# Sch5PowerControlCenter.net
KiCad netlist of a schematic drawn in Altium Designer
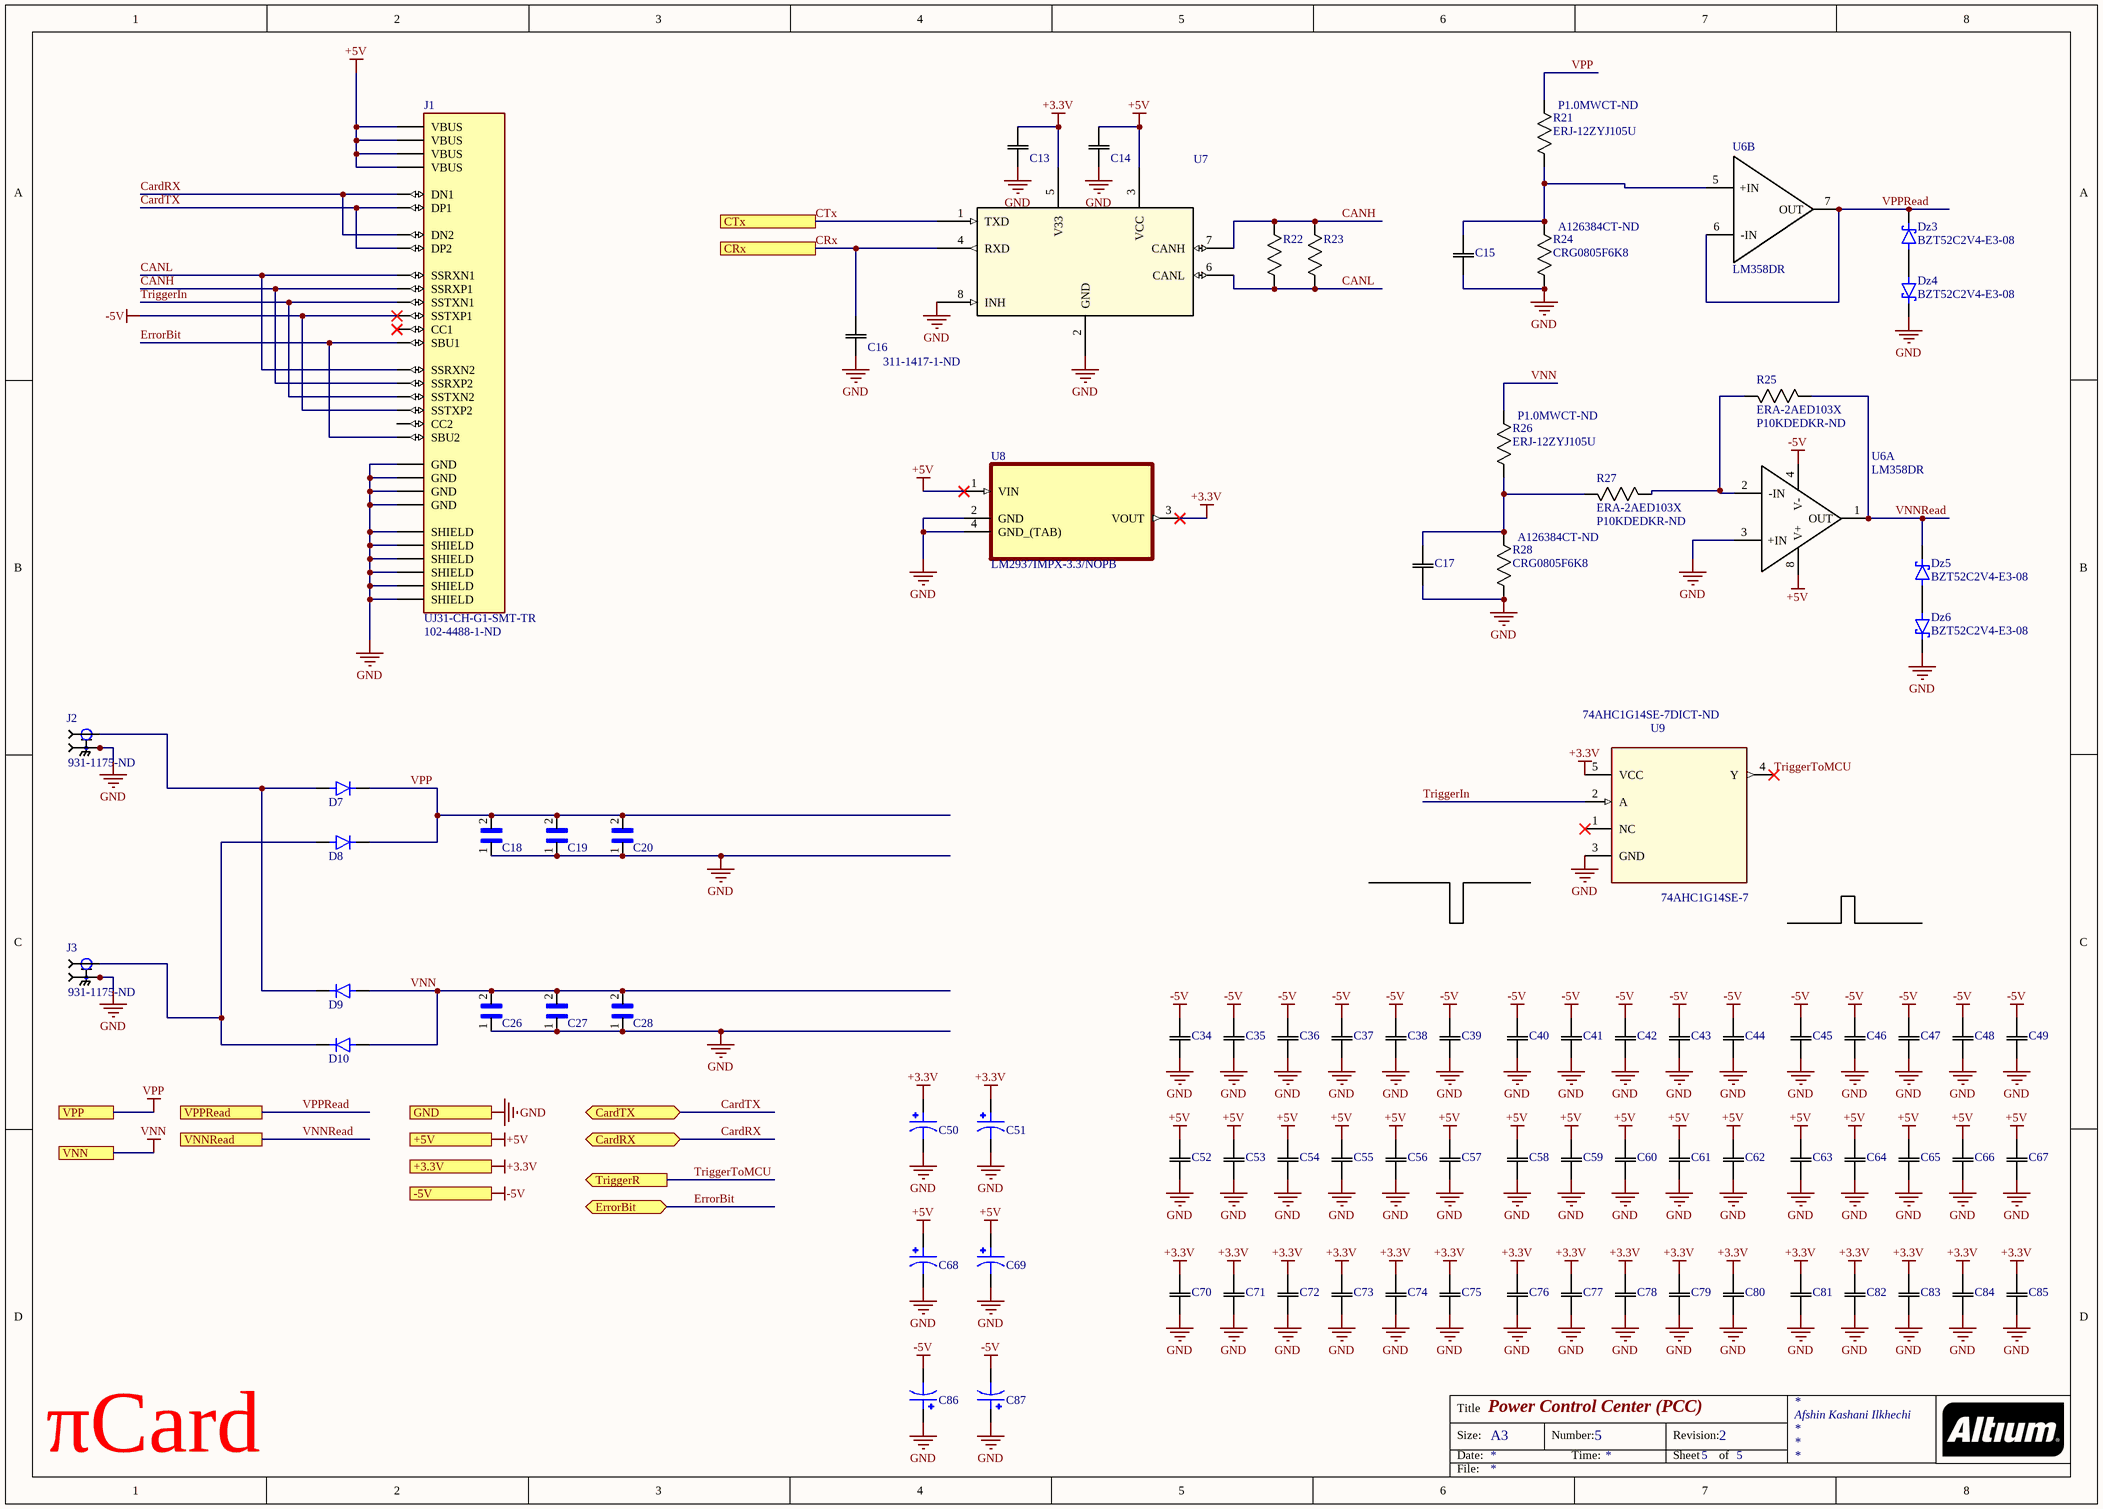
[diagram p0: Sch5PowerControlCenter.SchDoc]

(export (version "E")
  (design (tool "Eeschema 10.0.6"))
  (components
    (comp (ref "C13")
      (value "GRM155R71C103MA01D")
      (footprint "C0402")
      (libsource (lib "Afshin Library") (part "Cap_0402"))
    )
    (comp (ref "C14")
      (value "GRM155R71C103MA01D")
      (footprint "C0402")
      (libsource (lib "Afshin Library") (part "Cap_0402"))
    )
    (comp (ref "C15")
      (value "C0805C104Z5VACTU")
      (footprint "C0805")
      (libsource (lib "Afshin Library") (part "Cap_0805"))
    )
    (comp (ref "C16")
      (value "CC0402JRNPO9BN200")
      (footprint "C0402")
      (fields (field (name "SUPPLIER PART NUMBER 1") "311-1417-1-ND"))
      (libsource (lib "Afshin Library") (part "Cap_0402"))
    )
    (comp (ref "C17")
      (value "C0805C104Z5VACTU")
      (footprint "C0805")
      (libsource (lib "Afshin Library") (part "Cap_0805"))
    )
    (comp (ref "C18")
      (value "2220Y5000105KXTWS2")
      (footprint "CAPC5750X450N")
      (description "1ÂµF Â±10% 500V Ceramic Capacitor X7R 2220 (5750 Metric)")
      (fields (field (name "MF") "Syfer"))
      (libsource (lib "Afshin Library") (part "2220Y5000105KXTWS2"))
    )
    (comp (ref "C19")
      (value "2220Y5000105KXTWS2")
      (footprint "CAPC5750X450N")
      (description "1ÂµF Â±10% 500V Ceramic Capacitor X7R 2220 (5750 Metric)")
      (fields (field (name "MF") "Syfer"))
      (libsource (lib "Afshin Library") (part "2220Y5000105KXTWS2"))
    )
    (comp (ref "C20")
      (value "2220Y5000105KXTWS2")
      (footprint "CAPC5750X450N")
      (description "1ÂµF Â±10% 500V Ceramic Capacitor X7R 2220 (5750 Metric)")
      (fields (field (name "MF") "Syfer"))
      (libsource (lib "Afshin Library") (part "2220Y5000105KXTWS2"))
    )
    (comp (ref "C26")
      (value "2220Y5000105KXTWS2")
      (footprint "CAPC5750X450N")
      (description "1ÂµF Â±10% 500V Ceramic Capacitor X7R 2220 (5750 Metric)")
      (fields (field (name "MF") "Syfer"))
      (libsource (lib "Afshin Library") (part "2220Y5000105KXTWS2"))
    )
    (comp (ref "C27")
      (value "2220Y5000105KXTWS2")
      (footprint "CAPC5750X450N")
      (description "1ÂµF Â±10% 500V Ceramic Capacitor X7R 2220 (5750 Metric)")
      (fields (field (name "MF") "Syfer"))
      (libsource (lib "Afshin Library") (part "2220Y5000105KXTWS2"))
    )
    (comp (ref "C28")
      (value "2220Y5000105KXTWS2")
      (footprint "CAPC5750X450N")
      (description "1ÂµF Â±10% 500V Ceramic Capacitor X7R 2220 (5750 Metric)")
      (fields (field (name "MF") "Syfer"))
      (libsource (lib "Afshin Library") (part "2220Y5000105KXTWS2"))
    )
    (comp (ref "C34")
      (value "GRM155R71C103MA01D")
      (footprint "C0402")
      (libsource (lib "Afshin Library") (part "Cap_0402"))
    )
    (comp (ref "C35")
      (value "GRM155R71C103MA01D")
      (footprint "C0402")
      (libsource (lib "Afshin Library") (part "Cap_0402"))
    )
    (comp (ref "C36")
      (value "GRM155R71C103MA01D")
      (footprint "C0402")
      (libsource (lib "Afshin Library") (part "Cap_0402"))
    )
    (comp (ref "C37")
      (value "GRM155R71C103MA01D")
      (footprint "C0402")
      (libsource (lib "Afshin Library") (part "Cap_0402"))
    )
    (comp (ref "C38")
      (value "GRM155R71C103MA01D")
      (footprint "C0402")
      (libsource (lib "Afshin Library") (part "Cap_0402"))
    )
    (comp (ref "C39")
      (value "GRM155R71C103MA01D")
      (footprint "C0402")
      (libsource (lib "Afshin Library") (part "Cap_0402"))
    )
    (comp (ref "C40")
      (value "C0805C104Z5VACTU")
      (footprint "C0805")
      (libsource (lib "Afshin Library") (part "Cap_0805"))
    )
    (comp (ref "C41")
      (value "C0805C104Z5VACTU")
      (footprint "C0805")
      (libsource (lib "Afshin Library") (part "Cap_0805"))
    )
    (comp (ref "C42")
      (value "C0805C104Z5VACTU")
      (footprint "C0805")
      (libsource (lib "Afshin Library") (part "Cap_0805"))
    )
    (comp (ref "C43")
      (value "C0805C104Z5VACTU")
      (footprint "C0805")
      (libsource (lib "Afshin Library") (part "Cap_0805"))
    )
    (comp (ref "C44")
      (value "C0805C104Z5VACTU")
      (footprint "C0805")
      (libsource (lib "Afshin Library") (part "Cap_0805"))
    )
    (comp (ref "C45")
      (value "GRM155R71H102KA01J")
      (footprint "C0402")
      (libsource (lib "Afshin Library") (part "Cap_0402"))
    )
    (comp (ref "C46")
      (value "GRM155R71H102KA01J")
      (footprint "C0402")
      (libsource (lib "Afshin Library") (part "Cap_0402"))
    )
    (comp (ref "C47")
      (value "GRM155R71H102KA01J")
      (footprint "C0402")
      (libsource (lib "Afshin Library") (part "Cap_0402"))
    )
    (comp (ref "C48")
      (value "GRM155R71H102KA01J")
      (footprint "C0402")
      (libsource (lib "Afshin Library") (part "Cap_0402"))
    )
    (comp (ref "C49")
      (value "GRM155R71H102KA01J")
      (footprint "C0402")
      (libsource (lib "Afshin Library") (part "Cap_0402"))
    )
    (comp (ref "C50")
      (value "T55A107M6R3C0200")
      (footprint "C1206")
      (description "Tantalium")
      (libsource (lib "Afshin Library") (part "Cap_1206"))
    )
    (comp (ref "C51")
      (value "T55A107M6R3C0200")
      (footprint "C1206")
      (description "Tantalium")
      (libsource (lib "Afshin Library") (part "Cap_1206"))
    )
    (comp (ref "C52")
      (value "GRM155R71C103MA01D")
      (footprint "C0402")
      (libsource (lib "Afshin Library") (part "Cap_0402"))
    )
    (comp (ref "C53")
      (value "GRM155R71C103MA01D")
      (footprint "C0402")
      (libsource (lib "Afshin Library") (part "Cap_0402"))
    )
    (comp (ref "C54")
      (value "GRM155R71C103MA01D")
      (footprint "C0402")
      (libsource (lib "Afshin Library") (part "Cap_0402"))
    )
    (comp (ref "C55")
      (value "GRM155R71C103MA01D")
      (footprint "C0402")
      (libsource (lib "Afshin Library") (part "Cap_0402"))
    )
    (comp (ref "C56")
      (value "GRM155R71C103MA01D")
      (footprint "C0402")
      (libsource (lib "Afshin Library") (part "Cap_0402"))
    )
    (comp (ref "C57")
      (value "GRM155R71C103MA01D")
      (footprint "C0402")
      (libsource (lib "Afshin Library") (part "Cap_0402"))
    )
    (comp (ref "C58")
      (value "C0805C104Z5VACTU")
      (footprint "C0805")
      (libsource (lib "Afshin Library") (part "Cap_0805"))
    )
    (comp (ref "C59")
      (value "C0805C104Z5VACTU")
      (footprint "C0805")
      (libsource (lib "Afshin Library") (part "Cap_0805"))
    )
    (comp (ref "C60")
      (value "C0805C104Z5VACTU")
      (footprint "C0805")
      (libsource (lib "Afshin Library") (part "Cap_0805"))
    )
    (comp (ref "C61")
      (value "C0805C104Z5VACTU")
      (footprint "C0805")
      (libsource (lib "Afshin Library") (part "Cap_0805"))
    )
    (comp (ref "C62")
      (value "C0805C104Z5VACTU")
      (footprint "C0805")
      (libsource (lib "Afshin Library") (part "Cap_0805"))
    )
    (comp (ref "C63")
      (value "GRM155R71H102KA01J")
      (footprint "C0402")
      (libsource (lib "Afshin Library") (part "Cap_0402"))
    )
    (comp (ref "C64")
      (value "GRM155R71H102KA01J")
      (footprint "C0402")
      (libsource (lib "Afshin Library") (part "Cap_0402"))
    )
    (comp (ref "C65")
      (value "GRM155R71H102KA01J")
      (footprint "C0402")
      (libsource (lib "Afshin Library") (part "Cap_0402"))
    )
    (comp (ref "C66")
      (value "GRM155R71H102KA01J")
      (footprint "C0402")
      (libsource (lib "Afshin Library") (part "Cap_0402"))
    )
    (comp (ref "C67")
      (value "GRM155R71H102KA01J")
      (footprint "C0402")
      (libsource (lib "Afshin Library") (part "Cap_0402"))
    )
    (comp (ref "C68")
      (value "T55A107M6R3C0200")
      (footprint "C1206")
      (description "Tantalium")
      (libsource (lib "Afshin Library") (part "Cap_1206"))
    )
    (comp (ref "C69")
      (value "T55A107M6R3C0200")
      (footprint "C1206")
      (description "Tantalium")
      (libsource (lib "Afshin Library") (part "Cap_1206"))
    )
    (comp (ref "C70")
      (value "GRM155R71C103MA01D")
      (footprint "C0402")
      (libsource (lib "Afshin Library") (part "Cap_0402"))
    )
    (comp (ref "C71")
      (value "GRM155R71C103MA01D")
      (footprint "C0402")
      (libsource (lib "Afshin Library") (part "Cap_0402"))
    )
    (comp (ref "C72")
      (value "GRM155R71C103MA01D")
      (footprint "C0402")
      (libsource (lib "Afshin Library") (part "Cap_0402"))
    )
    (comp (ref "C73")
      (value "GRM155R71C103MA01D")
      (footprint "C0402")
      (libsource (lib "Afshin Library") (part "Cap_0402"))
    )
    (comp (ref "C74")
      (value "GRM155R71C103MA01D")
      (footprint "C0402")
      (libsource (lib "Afshin Library") (part "Cap_0402"))
    )
    (comp (ref "C75")
      (value "GRM155R71C103MA01D")
      (footprint "C0402")
      (libsource (lib "Afshin Library") (part "Cap_0402"))
    )
    (comp (ref "C76")
      (value "C0805C104Z5VACTU")
      (footprint "C0805")
      (libsource (lib "Afshin Library") (part "Cap_0805"))
    )
    (comp (ref "C77")
      (value "C0805C104Z5VACTU")
      (footprint "C0805")
      (libsource (lib "Afshin Library") (part "Cap_0805"))
    )
    (comp (ref "C78")
      (value "C0805C104Z5VACTU")
      (footprint "C0805")
      (libsource (lib "Afshin Library") (part "Cap_0805"))
    )
    (comp (ref "C79")
      (value "C0805C104Z5VACTU")
      (footprint "C0805")
      (libsource (lib "Afshin Library") (part "Cap_0805"))
    )
    (comp (ref "C80")
      (value "C0805C104Z5VACTU")
      (footprint "C0805")
      (libsource (lib "Afshin Library") (part "Cap_0805"))
    )
    (comp (ref "C81")
      (value "GRM155R71H102KA01J")
      (footprint "C0402")
      (libsource (lib "Afshin Library") (part "Cap_0402"))
    )
    (comp (ref "C82")
      (value "GRM155R71H102KA01J")
      (footprint "C0402")
      (libsource (lib "Afshin Library") (part "Cap_0402"))
    )
    (comp (ref "C83")
      (value "GRM155R71H102KA01J")
      (footprint "C0402")
      (libsource (lib "Afshin Library") (part "Cap_0402"))
    )
    (comp (ref "C84")
      (value "GRM155R71H102KA01J")
      (footprint "C0402")
      (libsource (lib "Afshin Library") (part "Cap_0402"))
    )
    (comp (ref "C85")
      (value "GRM155R71H102KA01J")
      (footprint "C0402")
      (libsource (lib "Afshin Library") (part "Cap_0402"))
    )
    (comp (ref "C86")
      (value "T55A107M6R3C0200")
      (footprint "C1206")
      (description "Tantalium")
      (libsource (lib "") (part "Cap_1206_1"))
    )
    (comp (ref "C87")
      (value "T55A107M6R3C0200")
      (footprint "C1206")
      (description "Tantalium")
      (libsource (lib "") (part "Cap_1206_1"))
    )
    (comp (ref "D7")
      (value "CD1408-R11000")
      (footprint "CD1408")
      (description "Diode Standard 1000V 1A Surface Mount 1408")
      (libsource (lib "Afshin Library") (part "CD1408-R11000"))
    )
    (comp (ref "D8")
      (value "CD1408-R11000")
      (footprint "CD1408")
      (description "Diode Standard 1000V 1A Surface Mount 1408")
      (libsource (lib "Afshin Library") (part "CD1408-R11000"))
    )
    (comp (ref "D9")
      (value "CD1408-R11000")
      (footprint "CD1408")
      (description "Diode Standard 1000V 1A Surface Mount 1408")
      (libsource (lib "Afshin Library") (part "CD1408-R11000"))
    )
    (comp (ref "D10")
      (value "CD1408-R11000")
      (footprint "CD1408")
      (description "Diode Standard 1000V 1A Surface Mount 1408")
      (libsource (lib "Afshin Library") (part "CD1408-R11000"))
    )
    (comp (ref "Dz3")
      (value "BZT52C2V4-E3-08")
      (footprint "SOD-123")
      (description "Zener Diode 2.4V 410mW ±5% Surface Mount SOD-123")
      (libsource (lib "Afshin Library") (part "BZT52C2V4-E3-08"))
    )
    (comp (ref "Dz4")
      (value "BZT52C2V4-E3-08")
      (footprint "SOD-123")
      (description "Zener Diode 2.4V 410mW ±5% Surface Mount SOD-123")
      (libsource (lib "Afshin Library") (part "BZT52C2V4-E3-08"))
    )
    (comp (ref "Dz5")
      (value "BZT52C2V4-E3-08")
      (footprint "SOD-123")
      (description "Zener Diode 2.4V 410mW ±5% Surface Mount SOD-123")
      (libsource (lib "Afshin Library") (part "BZT52C2V4-E3-08"))
    )
    (comp (ref "Dz6")
      (value "BZT52C2V4-E3-08")
      (footprint "SOD-123")
      (description "Zener Diode 2.4V 410mW ±5% Surface Mount SOD-123")
      (libsource (lib "Afshin Library") (part "BZT52C2V4-E3-08"))
    )
    (comp (ref "J1")
      (value "UJ31-CH-G1-SMT-TR")
      (footprint "CUI_UJ31-CH-G1-SMT-TR")
      (description "Type C, USB 3.1 Gen 2, 5 A, Right Angle, Surface Mount _SMT_ , USB Receptacle")
      (fields (field (name "MF") "CUI Devices") (field (name "SUPPLIER PART NUMBER 1") "102-4488-1-ND"))
      (libsource (lib "Afshin Library") (part "UJ31-CH-G1-SMT-TR"))
    )
    (comp (ref "J2")
      (value "EMPCB.SMAFSTJ.B.HT")
      (footprint "*TAOGLAS_EMPCB.SMAFSTJ.B.HT_EMPCB.SMAFSTJ.B.HT(Primary)")
      (description "SMA Connector Jack, Female Socket 50Ohm Board Edge, End Launch Solder")
      (fields
        (field (name "MF") "Taoglas Limited")
        (field (name "DIGI-KEY_PART_NUMBER") "931-1175-ND")
        (field (name "SUPPLIER PART NUMBER 1") "931-1175-ND")
      )
      (libsource (lib "Afshin Library") (part "EMPCB.SMAFSTJ.B.HT"))
    )
    (comp (ref "J3")
      (value "EMPCB.SMAFSTJ.B.HT")
      (footprint "*TAOGLAS_EMPCB.SMAFSTJ.B.HT_EMPCB.SMAFSTJ.B.HT(Primary)")
      (description "SMA Connector Jack, Female Socket 50Ohm Board Edge, End Launch Solder")
      (fields
        (field (name "MF") "Taoglas Limited")
        (field (name "DIGI-KEY_PART_NUMBER") "931-1175-ND")
        (field (name "SUPPLIER PART NUMBER 1") "931-1175-ND")
      )
      (libsource (lib "Afshin Library") (part "EMPCB.SMAFSTJ.B.HT"))
    )
    (comp (ref "R21")
      (value "ERJ-12ZYJ105U")
      (footprint "R2010")
      (description "Chip Resistor 2010 (5025 Metric) Automotive AEC-Q200 Thick Film")
      (fields (field (name "SUPPLIER PART NUMBER 1") "P1.0MWCT-ND"))
      (libsource (lib "Afshin Library") (part "Res_2010"))
    )
    (comp (ref "R22")
      (value "CRGCQ0805F120R")
      (footprint "0805")
      (libsource (lib "Afshin Library") (part "Res_0805"))
    )
    (comp (ref "R23")
      (value "CRGCQ0805F120R")
      (footprint "0805")
      (libsource (lib "Afshin Library") (part "Res_0805"))
    )
    (comp (ref "R24")
      (value "CRG0805F6K8")
      (footprint "0805")
      (fields (field (name "SUPPLIER PART NUMBER 1") "A126384CT-ND"))
      (libsource (lib "Afshin Library") (part "Res_0805"))
    )
    (comp (ref "R25")
      (value "ERA-2AED103X")
      (footprint "R0402")
      (fields (field (name "SUPPLIER PART NUMBER 1") "P10KDEDKR-ND"))
      (libsource (lib "Afshin Library") (part "Res_0805"))
    )
    (comp (ref "R26")
      (value "ERJ-12ZYJ105U")
      (footprint "R2010")
      (description "Chip Resistor 2010 (5025 Metric) Automotive AEC-Q200 Thick Film")
      (fields (field (name "SUPPLIER PART NUMBER 1") "P1.0MWCT-ND"))
      (libsource (lib "Afshin Library") (part "Res_2010"))
    )
    (comp (ref "R27")
      (value "ERA-2AED103X")
      (footprint "R0402")
      (fields (field (name "SUPPLIER PART NUMBER 1") "P10KDEDKR-ND"))
      (libsource (lib "Afshin Library") (part "Res_0805"))
    )
    (comp (ref "R28")
      (value "CRG0805F6K8")
      (footprint "0805")
      (fields (field (name "SUPPLIER PART NUMBER 1") "A126384CT-ND"))
      (libsource (lib "Afshin Library") (part "Res_0805"))
    )
    (comp (ref "U6")
      (value "LM358DR")
      (footprint "SOIC127P600X175-8N")
      (libsource (lib "Afshin Library") (part "LM358DR"))
    )
    (comp (ref "U7")
      (value "IFX1050GVIOXUMA1")
      (footprint "SOIC127P600X175-8N")
      (description "No Description Available")
      (fields
        (field (name "MANUFACTURER_PART_NUMBER") "IFX1050G")
        (field (name "COPYRIGHT") "Copyright (C) 2018 Accelerated Designs. All rights reserved")
      )
      (libsource (lib "Afshin Library") (part "IFX1050GVIOXUMA1"))
    )
    (comp (ref "U8")
      (value "LM2937IMPX-3.3/NOPB")
      (footprint "SOT230P700X180-4N")
      (description "Linear Voltage Regulator IC 1 Output 400mA SOT-223-4")
      (fields (field (name "MF") "Texas Instruments"))
      (libsource (lib "Afshin Library") (part "LM2937IMPX-3.3/NOPB"))
    )
    (comp (ref "U9")
      (value "74AHC1G14SE-7")
      (footprint "*SOT65P210X110-5N")
      (description "Inverter IC 1 Channel Schmitt Trigger SOT-353")
      (fields
        (field (name "DIGI-KEY_PART_NUMBER") "74AHC1G14SE-7DICT-ND")
        (field (name "MF") "Diodes Inc.")
        (field (name "SUPPLIER PART NUMBER 1") "74AHC1G14SE-7DICT-ND")
      )
      (libsource (lib "Afshin Library") (part "74AHC1G14SE-7"))
    )
  )
  (nets
    (net (code "1") (name "+3.3V") (class "Default")
      (node (ref "C13") (pin "2") (pinfunction "2_2") (pintype "passive"))
      (node (ref "C50") (pin "1") (pinfunction "POS_1") (pintype "passive"))
      (node (ref "C51") (pin "1") (pinfunction "POS_1") (pintype "passive"))
      (node (ref "C70") (pin "2") (pinfunction "2_2") (pintype "passive"))
      (node (ref "C71") (pin "2") (pinfunction "2_2") (pintype "passive"))
      (node (ref "C72") (pin "2") (pinfunction "2_2") (pintype "passive"))
      (node (ref "C73") (pin "2") (pinfunction "2_2") (pintype "passive"))
      (node (ref "C74") (pin "2") (pinfunction "2_2") (pintype "passive"))
      (node (ref "C75") (pin "2") (pinfunction "2_2") (pintype "passive"))
      (node (ref "C76") (pin "2") (pinfunction "2_2") (pintype "passive"))
      (node (ref "C77") (pin "2") (pinfunction "2_2") (pintype "passive"))
      (node (ref "C78") (pin "2") (pinfunction "2_2") (pintype "passive"))
      (node (ref "C79") (pin "2") (pinfunction "2_2") (pintype "passive"))
      (node (ref "C80") (pin "2") (pinfunction "2_2") (pintype "passive"))
      (node (ref "C81") (pin "2") (pinfunction "2_2") (pintype "passive"))
      (node (ref "C82") (pin "2") (pinfunction "2_2") (pintype "passive"))
      (node (ref "C83") (pin "2") (pinfunction "2_2") (pintype "passive"))
      (node (ref "C84") (pin "2") (pinfunction "2_2") (pintype "passive"))
      (node (ref "C85") (pin "2") (pinfunction "2_2") (pintype "passive"))
      (node (ref "U7") (pin "5") (pinfunction "V33_5") (pintype "power_in"))
      (node (ref "U8") (pin "3") (pinfunction "VOUT_3") (pintype "output"))
      (node (ref "U9") (pin "5") (pinfunction "VCC_5") (pintype "power_in"))
    )
    (net (code "2") (name "+5V") (class "Default")
      (node (ref "C14") (pin "2") (pinfunction "2_2") (pintype "passive"))
      (node (ref "C52") (pin "2") (pinfunction "2_2") (pintype "passive"))
      (node (ref "C53") (pin "2") (pinfunction "2_2") (pintype "passive"))
      (node (ref "C54") (pin "2") (pinfunction "2_2") (pintype "passive"))
      (node (ref "C55") (pin "2") (pinfunction "2_2") (pintype "passive"))
      (node (ref "C56") (pin "2") (pinfunction "2_2") (pintype "passive"))
      (node (ref "C57") (pin "2") (pinfunction "2_2") (pintype "passive"))
      (node (ref "C58") (pin "2") (pinfunction "2_2") (pintype "passive"))
      (node (ref "C59") (pin "2") (pinfunction "2_2") (pintype "passive"))
      (node (ref "C60") (pin "2") (pinfunction "2_2") (pintype "passive"))
      (node (ref "C61") (pin "2") (pinfunction "2_2") (pintype "passive"))
      (node (ref "C62") (pin "2") (pinfunction "2_2") (pintype "passive"))
      (node (ref "C63") (pin "2") (pinfunction "2_2") (pintype "passive"))
      (node (ref "C64") (pin "2") (pinfunction "2_2") (pintype "passive"))
      (node (ref "C65") (pin "2") (pinfunction "2_2") (pintype "passive"))
      (node (ref "C66") (pin "2") (pinfunction "2_2") (pintype "passive"))
      (node (ref "C67") (pin "2") (pinfunction "2_2") (pintype "passive"))
      (node (ref "C68") (pin "1") (pinfunction "POS_1") (pintype "passive"))
      (node (ref "C69") (pin "1") (pinfunction "POS_1") (pintype "passive"))
      (node (ref "J1") (pin "A4") (pinfunction "VBUS_A4") (pintype "power_in"))
      (node (ref "J1") (pin "A9") (pinfunction "VBUS_A9") (pintype "power_in"))
      (node (ref "J1") (pin "B4") (pinfunction "VBUS_B4") (pintype "power_in"))
      (node (ref "J1") (pin "B9") (pinfunction "VBUS_B9") (pintype "power_in"))
      (node (ref "U6") (pin "8") (pinfunction "V+_8") (pintype "power_in"))
      (node (ref "U7") (pin "3") (pinfunction "VCC_3") (pintype "power_in"))
      (node (ref "U8") (pin "1") (pinfunction "VIN_1") (pintype "input"))
    )
    (net (code "3") (name "-5V") (class "Default")
      (node (ref "C34") (pin "2") (pinfunction "2_2") (pintype "passive"))
      (node (ref "C35") (pin "2") (pinfunction "2_2") (pintype "passive"))
      (node (ref "C36") (pin "2") (pinfunction "2_2") (pintype "passive"))
      (node (ref "C37") (pin "2") (pinfunction "2_2") (pintype "passive"))
      (node (ref "C38") (pin "2") (pinfunction "2_2") (pintype "passive"))
      (node (ref "C39") (pin "2") (pinfunction "2_2") (pintype "passive"))
      (node (ref "C40") (pin "2") (pinfunction "2_2") (pintype "passive"))
      (node (ref "C41") (pin "2") (pinfunction "2_2") (pintype "passive"))
      (node (ref "C42") (pin "2") (pinfunction "2_2") (pintype "passive"))
      (node (ref "C43") (pin "2") (pinfunction "2_2") (pintype "passive"))
      (node (ref "C44") (pin "2") (pinfunction "2_2") (pintype "passive"))
      (node (ref "C45") (pin "2") (pinfunction "2_2") (pintype "passive"))
      (node (ref "C46") (pin "2") (pinfunction "2_2") (pintype "passive"))
      (node (ref "C47") (pin "2") (pinfunction "2_2") (pintype "passive"))
      (node (ref "C48") (pin "2") (pinfunction "2_2") (pintype "passive"))
      (node (ref "C49") (pin "2") (pinfunction "2_2") (pintype "passive"))
      (node (ref "C86") (pin "2") (pinfunction "NEG_2") (pintype "passive"))
      (node (ref "C87") (pin "2") (pinfunction "NEG_2") (pintype "passive"))
      (node (ref "J1") (pin "A2") (pinfunction "SSTXP1_A2") (pintype "bidirectional"))
      (node (ref "J1") (pin "B2") (pinfunction "SSTXP2_B2") (pintype "bidirectional"))
      (node (ref "U6") (pin "4") (pinfunction "V-_4") (pintype "power_in"))
    )
    (net (code "4") (name "/CANH") (class "Default")
      (node (ref "J1") (pin "A11") (pinfunction "SSRXP2_A11") (pintype "bidirectional"))
      (node (ref "J1") (pin "B11") (pinfunction "SSRXP1_B11") (pintype "bidirectional"))
      (node (ref "R22") (pin "2") (pinfunction "2_2") (pintype "passive"))
      (node (ref "R23") (pin "2") (pinfunction "2_2") (pintype "passive"))
      (node (ref "U7") (pin "7") (pinfunction "CANH_7") (pintype "bidirectional"))
    )
    (net (code "5") (name "/CANL") (class "Default")
      (node (ref "J1") (pin "A10") (pinfunction "SSRXN2_A10") (pintype "bidirectional"))
      (node (ref "J1") (pin "B10") (pinfunction "SSRXN1_B10") (pintype "bidirectional"))
      (node (ref "R22") (pin "1") (pinfunction "1_1") (pintype "passive"))
      (node (ref "R23") (pin "1") (pinfunction "1_1") (pintype "passive"))
      (node (ref "U7") (pin "6") (pinfunction "CANL_6") (pintype "bidirectional"))
    )
    (net (code "6") (name "/CRx") (class "Default")
      (node (ref "C16") (pin "2") (pinfunction "2_2") (pintype "passive"))
      (node (ref "U7") (pin "4") (pinfunction "RXD_4") (pintype "output"))
    )
    (net (code "7") (name "/CTx") (class "Default")
      (node (ref "U7") (pin "1") (pinfunction "TXD_1") (pintype "input"))
    )
    (net (code "8") (name "/CardRX") (class "Default")
      (node (ref "J1") (pin "A7") (pinfunction "DN1_A7") (pintype "bidirectional"))
      (node (ref "J1") (pin "B7") (pinfunction "DN2_B7") (pintype "bidirectional"))
    )
    (net (code "9") (name "/CardTX") (class "Default")
      (node (ref "J1") (pin "A6") (pinfunction "DP1_A6") (pintype "bidirectional"))
      (node (ref "J1") (pin "B6") (pinfunction "DP2_B6") (pintype "bidirectional"))
    )
    (net (code "10") (name "/ErrorBit") (class "Default")
      (node (ref "J1") (pin "A8") (pinfunction "SBU1_A8") (pintype "bidirectional"))
      (node (ref "J1") (pin "B8") (pinfunction "SBU2_B8") (pintype "bidirectional"))
    )
    (net (code "11") (name "/TriggerIn") (class "Default")
      (node (ref "J1") (pin "A3") (pinfunction "SSTXN1_A3") (pintype "bidirectional"))
      (node (ref "J1") (pin "B3") (pinfunction "SSTXN2_B3") (pintype "bidirectional"))
      (node (ref "U9") (pin "2") (pinfunction "A_2") (pintype "input"))
    )
    (net (code "12") (name "/TriggerToMCU") (class "Default")
      (node (ref "U9") (pin "4") (pinfunction "Y_4") (pintype "output"))
    )
    (net (code "13") (name "/VNNRead") (class "Default")
      (node (ref "Dz5") (pin "1") (pinfunction "K_1") (pintype "passive"))
      (node (ref "R25") (pin "2") (pinfunction "2_2") (pintype "passive"))
      (node (ref "U6") (pin "1") (pinfunction "OUT_1") (pintype "passive"))
    )
    (net (code "14") (name "/VPPRead") (class "Default")
      (node (ref "Dz3") (pin "1") (pinfunction "K_1") (pintype "passive"))
      (node (ref "U6") (pin "6") (pinfunction "-IN_6") (pintype "passive"))
      (node (ref "U6") (pin "7") (pinfunction "OUT_7") (pintype "passive"))
    )
    (net (code "15") (name "GND") (class "Default")
      (node (ref "C13") (pin "1") (pinfunction "1_1") (pintype "passive"))
      (node (ref "C14") (pin "1") (pinfunction "1_1") (pintype "passive"))
      (node (ref "C15") (pin "1") (pinfunction "1_1") (pintype "passive"))
      (node (ref "C16") (pin "1") (pinfunction "1_1") (pintype "passive"))
      (node (ref "C17") (pin "1") (pinfunction "1_1") (pintype "passive"))
      (node (ref "C18") (pin "1") (pinfunction "1_1") (pintype "passive"))
      (node (ref "C19") (pin "1") (pinfunction "1_1") (pintype "passive"))
      (node (ref "C20") (pin "1") (pinfunction "1_1") (pintype "passive"))
      (node (ref "C26") (pin "1") (pinfunction "1_1") (pintype "passive"))
      (node (ref "C27") (pin "1") (pinfunction "1_1") (pintype "passive"))
      (node (ref "C28") (pin "1") (pinfunction "1_1") (pintype "passive"))
      (node (ref "C34") (pin "1") (pinfunction "1_1") (pintype "passive"))
      (node (ref "C35") (pin "1") (pinfunction "1_1") (pintype "passive"))
      (node (ref "C36") (pin "1") (pinfunction "1_1") (pintype "passive"))
      (node (ref "C37") (pin "1") (pinfunction "1_1") (pintype "passive"))
      (node (ref "C38") (pin "1") (pinfunction "1_1") (pintype "passive"))
      (node (ref "C39") (pin "1") (pinfunction "1_1") (pintype "passive"))
      (node (ref "C40") (pin "1") (pinfunction "1_1") (pintype "passive"))
      (node (ref "C41") (pin "1") (pinfunction "1_1") (pintype "passive"))
      (node (ref "C42") (pin "1") (pinfunction "1_1") (pintype "passive"))
      (node (ref "C43") (pin "1") (pinfunction "1_1") (pintype "passive"))
      (node (ref "C44") (pin "1") (pinfunction "1_1") (pintype "passive"))
      (node (ref "C45") (pin "1") (pinfunction "1_1") (pintype "passive"))
      (node (ref "C46") (pin "1") (pinfunction "1_1") (pintype "passive"))
      (node (ref "C47") (pin "1") (pinfunction "1_1") (pintype "passive"))
      (node (ref "C48") (pin "1") (pinfunction "1_1") (pintype "passive"))
      (node (ref "C49") (pin "1") (pinfunction "1_1") (pintype "passive"))
      (node (ref "C50") (pin "2") (pinfunction "NEG_2") (pintype "passive"))
      (node (ref "C51") (pin "2") (pinfunction "NEG_2") (pintype "passive"))
      (node (ref "C52") (pin "1") (pinfunction "1_1") (pintype "passive"))
      (node (ref "C53") (pin "1") (pinfunction "1_1") (pintype "passive"))
      (node (ref "C54") (pin "1") (pinfunction "1_1") (pintype "passive"))
      (node (ref "C55") (pin "1") (pinfunction "1_1") (pintype "passive"))
      (node (ref "C56") (pin "1") (pinfunction "1_1") (pintype "passive"))
      (node (ref "C57") (pin "1") (pinfunction "1_1") (pintype "passive"))
      (node (ref "C58") (pin "1") (pinfunction "1_1") (pintype "passive"))
      (node (ref "C59") (pin "1") (pinfunction "1_1") (pintype "passive"))
      (node (ref "C60") (pin "1") (pinfunction "1_1") (pintype "passive"))
      (node (ref "C61") (pin "1") (pinfunction "1_1") (pintype "passive"))
      (node (ref "C62") (pin "1") (pinfunction "1_1") (pintype "passive"))
      (node (ref "C63") (pin "1") (pinfunction "1_1") (pintype "passive"))
      (node (ref "C64") (pin "1") (pinfunction "1_1") (pintype "passive"))
      (node (ref "C65") (pin "1") (pinfunction "1_1") (pintype "passive"))
      (node (ref "C66") (pin "1") (pinfunction "1_1") (pintype "passive"))
      (node (ref "C67") (pin "1") (pinfunction "1_1") (pintype "passive"))
      (node (ref "C68") (pin "2") (pinfunction "NEG_2") (pintype "passive"))
      (node (ref "C69") (pin "2") (pinfunction "NEG_2") (pintype "passive"))
      (node (ref "C70") (pin "1") (pinfunction "1_1") (pintype "passive"))
      (node (ref "C71") (pin "1") (pinfunction "1_1") (pintype "passive"))
      (node (ref "C72") (pin "1") (pinfunction "1_1") (pintype "passive"))
      (node (ref "C73") (pin "1") (pinfunction "1_1") (pintype "passive"))
      (node (ref "C74") (pin "1") (pinfunction "1_1") (pintype "passive"))
      (node (ref "C75") (pin "1") (pinfunction "1_1") (pintype "passive"))
      (node (ref "C76") (pin "1") (pinfunction "1_1") (pintype "passive"))
      (node (ref "C77") (pin "1") (pinfunction "1_1") (pintype "passive"))
      (node (ref "C78") (pin "1") (pinfunction "1_1") (pintype "passive"))
      (node (ref "C79") (pin "1") (pinfunction "1_1") (pintype "passive"))
      (node (ref "C80") (pin "1") (pinfunction "1_1") (pintype "passive"))
      (node (ref "C81") (pin "1") (pinfunction "1_1") (pintype "passive"))
      (node (ref "C82") (pin "1") (pinfunction "1_1") (pintype "passive"))
      (node (ref "C83") (pin "1") (pinfunction "1_1") (pintype "passive"))
      (node (ref "C84") (pin "1") (pinfunction "1_1") (pintype "passive"))
      (node (ref "C85") (pin "1") (pinfunction "1_1") (pintype "passive"))
      (node (ref "C86") (pin "1") (pinfunction "POS_1") (pintype "passive"))
      (node (ref "C87") (pin "1") (pinfunction "POS_1") (pintype "passive"))
      (node (ref "Dz4") (pin "1") (pinfunction "K_1") (pintype "passive"))
      (node (ref "Dz6") (pin "1") (pinfunction "K_1") (pintype "passive"))
      (node (ref "J1") (pin "A1") (pinfunction "GND_A1") (pintype "power_in"))
      (node (ref "J1") (pin "A12") (pinfunction "GND_A12") (pintype "power_in"))
      (node (ref "J1") (pin "B1") (pinfunction "GND_B1") (pintype "power_in"))
      (node (ref "J1") (pin "B12") (pinfunction "GND_B12") (pintype "power_in"))
      (node (ref "J1") (pin "SH1") (pinfunction "SHIELD_SH1") (pintype "power_in"))
      (node (ref "J1") (pin "SH2") (pinfunction "SHIELD_SH2") (pintype "power_in"))
      (node (ref "J1") (pin "SH3") (pinfunction "SHIELD_SH3") (pintype "power_in"))
      (node (ref "J1") (pin "SH4") (pinfunction "SHIELD_SH4") (pintype "power_in"))
      (node (ref "J1") (pin "SH5") (pinfunction "SHIELD_SH5") (pintype "power_in"))
      (node (ref "J1") (pin "SH6") (pinfunction "SHIELD_SH6") (pintype "power_in"))
      (node (ref "J2") (pin "SH1") (pinfunction "2_SH1") (pintype "passive"))
      (node (ref "J2") (pin "SH2") (pinfunction "2_SH2") (pintype "passive"))
      (node (ref "J2") (pin "SH3") (pinfunction "2_SH3") (pintype "passive"))
      (node (ref "J2") (pin "SH4") (pinfunction "2_SH4") (pintype "passive"))
      (node (ref "J3") (pin "SH1") (pinfunction "2_SH1") (pintype "passive"))
      (node (ref "J3") (pin "SH2") (pinfunction "2_SH2") (pintype "passive"))
      (node (ref "J3") (pin "SH3") (pinfunction "2_SH3") (pintype "passive"))
      (node (ref "J3") (pin "SH4") (pinfunction "2_SH4") (pintype "passive"))
      (node (ref "R24") (pin "1") (pinfunction "1_1") (pintype "passive"))
      (node (ref "R28") (pin "1") (pinfunction "1_1") (pintype "passive"))
      (node (ref "U6") (pin "3") (pinfunction "+IN_3") (pintype "passive"))
      (node (ref "U7") (pin "2") (pinfunction "GND_2") (pintype "power_in"))
      (node (ref "U7") (pin "8") (pinfunction "INH_8") (pintype "input"))
      (node (ref "U8") (pin "2") (pinfunction "GND_2") (pintype "passive"))
      (node (ref "U8") (pin "4") (pinfunction "GND_(TAB)_4") (pintype "passive"))
      (node (ref "U9") (pin "3") (pinfunction "GND_3") (pintype "passive"))
    )
    (net (code "16") (name "Net-(C17-Pad2)") (class "Default")
      (node (ref "C17") (pin "2") (pinfunction "2_2") (pintype "passive"))
      (node (ref "R26") (pin "1") (pinfunction "1_1") (pintype "passive"))
      (node (ref "R27") (pin "1") (pinfunction "1_1") (pintype "passive"))
      (node (ref "R28") (pin "2") (pinfunction "2_2") (pintype "passive"))
    )
    (net (code "17") (name "Net-(D7-Pad2)") (class "Default")
      (node (ref "D7") (pin "2") (pinfunction "2_2") (pintype "passive"))
      (node (ref "D9") (pin "1") (pinfunction "1_1") (pintype "passive"))
      (node (ref "J2") (pin "1") (pinfunction "1_1") (pintype "passive"))
    )
    (net (code "18") (name "Net-(D10-Pad1)") (class "Default")
      (node (ref "D10") (pin "1") (pinfunction "1_1") (pintype "passive"))
      (node (ref "D8") (pin "2") (pinfunction "2_2") (pintype "passive"))
      (node (ref "J3") (pin "1") (pinfunction "1_1") (pintype "passive"))
    )
    (net (code "19") (name "Net-(Dz3-A)") (class "Default")
      (node (ref "Dz3") (pin "2") (pinfunction "A_2") (pintype "passive"))
      (node (ref "Dz4") (pin "2") (pinfunction "A_2") (pintype "passive"))
    )
    (net (code "20") (name "Net-(Dz5-A)") (class "Default")
      (node (ref "Dz5") (pin "2") (pinfunction "A_2") (pintype "passive"))
      (node (ref "Dz6") (pin "2") (pinfunction "A_2") (pintype "passive"))
    )
    (net (code "21") (name "Net-(U6A--IN)") (class "Default")
      (node (ref "R25") (pin "1") (pinfunction "1_1") (pintype "passive"))
      (node (ref "R27") (pin "2") (pinfunction "2_2") (pintype "passive"))
      (node (ref "U6") (pin "2") (pinfunction "-IN_2") (pintype "passive"))
    )
    (net (code "22") (name "Net-(U6B-+IN)") (class "Default")
      (node (ref "C15") (pin "2") (pinfunction "2_2") (pintype "passive"))
      (node (ref "R21") (pin "1") (pinfunction "1_1") (pintype "passive"))
      (node (ref "R24") (pin "2") (pinfunction "2_2") (pintype "passive"))
      (node (ref "U6") (pin "5") (pinfunction "+IN_5") (pintype "passive"))
    )
    (net (code "23") (name "VNN") (class "Default")
      (node (ref "C26") (pin "2") (pinfunction "2_2") (pintype "passive"))
      (node (ref "C27") (pin "2") (pinfunction "2_2") (pintype "passive"))
      (node (ref "C28") (pin "2") (pinfunction "2_2") (pintype "passive"))
      (node (ref "D10") (pin "2") (pinfunction "2_2") (pintype "passive"))
      (node (ref "D9") (pin "2") (pinfunction "2_2") (pintype "passive"))
      (node (ref "R26") (pin "2") (pinfunction "2_2") (pintype "passive"))
    )
    (net (code "24") (name "VPP") (class "Default")
      (node (ref "C18") (pin "2") (pinfunction "2_2") (pintype "passive"))
      (node (ref "C19") (pin "2") (pinfunction "2_2") (pintype "passive"))
      (node (ref "C20") (pin "2") (pinfunction "2_2") (pintype "passive"))
      (node (ref "D7") (pin "1") (pinfunction "1_1") (pintype "passive"))
      (node (ref "D8") (pin "1") (pinfunction "1_1") (pintype "passive"))
      (node (ref "R21") (pin "2") (pinfunction "2_2") (pintype "passive"))
    )
    (net (code "25") (name "unconnected-(J1-CC1-PadA5)") (class "Default")
      (node (ref "J1") (pin "A5") (pinfunction "CC1_A5") (pintype "bidirectional+no_connect"))
    )
    (net (code "26") (name "unconnected-(J1-CC2-PadB5)") (class "Default")
      (node (ref "J1") (pin "B5") (pinfunction "CC2_B5") (pintype "bidirectional"))
    )
    (net (code "27") (name "unconnected-(U9-NC-Pad1)") (class "Default")
      (node (ref "U9") (pin "1") (pinfunction "NC_1") (pintype "passive+no_connect"))
    )
  )
)
